# MCU.net
KiCad netlist of a schematic drawn in Altium Designer
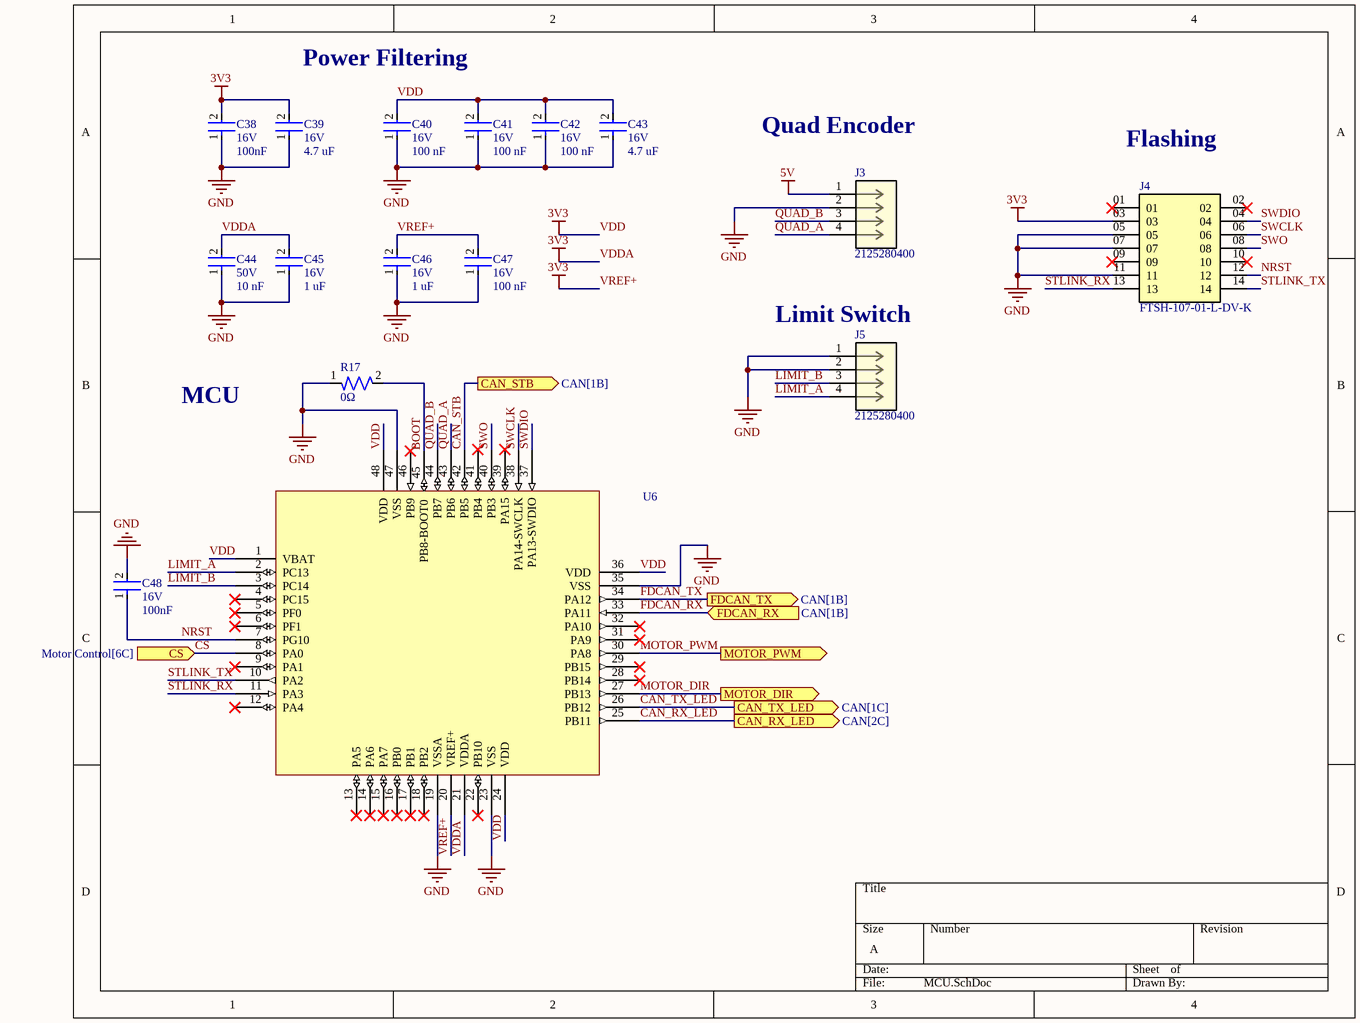
[diagram p0: MCU.SchDoc]

(export (version "E")
  (design (tool "Eeschema 10.0.6"))
  (components
    (comp (ref "C38")
      (value "CAP 0805")
      (footprint "CAP-0805")
      (fields (field (name "VOLTAGE RATING") "16V") (field (name "CAPACITANCE") "100nF"))
      (libsource (lib "EHW_27") (part "CAP 0805"))
    )
    (comp (ref "C39")
      (value "CAP 0805")
      (footprint "CAP-0805")
      (fields (field (name "VOLTAGE RATING") "16V") (field (name "CAPACITANCE") "4.7 uF"))
      (libsource (lib "EHW_27") (part "CAP 0805"))
    )
    (comp (ref "C40")
      (value "CAP 0805")
      (footprint "CAP-0805")
      (fields (field (name "VOLTAGE RATING") "16V") (field (name "CAPACITANCE") "100 nF"))
      (libsource (lib "EHW_27") (part "CAP 0805"))
    )
    (comp (ref "C41")
      (value "CAP 0805")
      (footprint "CAP-0805")
      (fields (field (name "VOLTAGE RATING") "16V") (field (name "CAPACITANCE") "100 nF"))
      (libsource (lib "EHW_27") (part "CAP 0805"))
    )
    (comp (ref "C42")
      (value "CAP 0805")
      (footprint "CAP-0805")
      (fields (field (name "VOLTAGE RATING") "16V") (field (name "CAPACITANCE") "100 nF"))
      (libsource (lib "EHW_27") (part "CAP 0805"))
    )
    (comp (ref "C43")
      (value "CAP 0805")
      (footprint "CAP-0805")
      (fields (field (name "VOLTAGE RATING") "16V") (field (name "CAPACITANCE") "4.7 uF"))
      (libsource (lib "EHW_27") (part "CAP 0805"))
    )
    (comp (ref "C44")
      (value "CAP 0805")
      (footprint "CAP-0805")
      (fields (field (name "VOLTAGE RATING") "50V") (field (name "CAPACITANCE") "10 nF"))
      (libsource (lib "EHW_27") (part "CAP 0805"))
    )
    (comp (ref "C45")
      (value "CAP 0805")
      (footprint "CAP-0805")
      (fields (field (name "VOLTAGE RATING") "16V") (field (name "CAPACITANCE") "1 uF"))
      (libsource (lib "EHW_27") (part "CAP 0805"))
    )
    (comp (ref "C46")
      (value "CAP 0805")
      (footprint "CAP-0805")
      (fields (field (name "VOLTAGE RATING") "16V") (field (name "CAPACITANCE") "1 uF"))
      (libsource (lib "EHW_27") (part "CAP 0805"))
    )
    (comp (ref "C47")
      (value "CAP 0805")
      (footprint "CAP-0805")
      (fields (field (name "VOLTAGE RATING") "16V") (field (name "CAPACITANCE") "100 nF"))
      (libsource (lib "EHW_27") (part "CAP 0805"))
    )
    (comp (ref "C48")
      (value "CAP 0805")
      (footprint "CAP-0805")
      (fields (field (name "VOLTAGE RATING") "16V") (field (name "CAPACITANCE") "100nF"))
      (libsource (lib "EHW_27") (part "CAP 0805"))
    )
    (comp (ref "J3")
      (value "2125280400")
      (footprint "CONN_2125280000_04_MOL")
      (fields (field (name "COPYRIGHT") "Copyright (C) 2026 Ultra Librarian. All rights reserved."))
      (libsource (lib "EHW_27") (part "CONN MF+ 4 PIN Right Angle Square"))
    )
    (comp (ref "J4")
      (value "FTSH-107-01-L-DV-K")
      (footprint "SAMTEC_FTSH-107-01-L-DV-K")
      (description "Connector Header Surface Mount 14 position 0.050\" (1.27mm)")
      (fields (field (name "MF") "Samtec"))
      (libsource (lib "EHW_27") (part "CONN_Flashing-0001"))
    )
    (comp (ref "J5")
      (value "2125280400")
      (footprint "CONN_2125280000_04_MOL")
      (fields (field (name "COPYRIGHT") "Copyright (C) 2026 Ultra Librarian. All rights reserved."))
      (libsource (lib "EHW_27") (part "CONN MF+ 4 PIN Right Angle Square"))
    )
    (comp (ref "R17")
      (value "CRF2010-J/-000ELF")
      (footprint "RES-2010")
      (description "0 Ohms Jumper Chip Resistor 2010 (5025 Metric) Automotive AEC-Q200 Metal Element")
      (fields (field (name "TOLERANCE") "1%") (field (name "RESISTANCE") "0Ω"))
      (libsource (lib "EHW_27") (part "RES-0-0001"))
    )
    (comp (ref "U6")
      (value "STM32G431CBT6")
      (footprint "IC-LQFP48")
      (description "IC MCU 32BIT 128KB FLASH 48LQFP")
      (libsource (lib "EHW_27") (part "IC-STM32G431CBT6"))
    )
  )
  (nets
    (net (code "1") (name "/BOOT") (class "Default")
      (node (ref "R17") (pin "2") (pinfunction "2_2") (pintype "passive"))
      (node (ref "U6") (pin "45") (pinfunction "PB8-BOOT0_45") (pintype "bidirectional"))
    )
    (net (code "2") (name "/CAN_RX_LED") (class "Default")
      (node (ref "U6") (pin "25") (pinfunction "PB11_25") (pintype "output"))
    )
    (net (code "3") (name "/CAN_STB") (class "Default")
      (node (ref "U6") (pin "42") (pinfunction "PB5_42") (pintype "bidirectional"))
    )
    (net (code "4") (name "/CAN_TX_LED") (class "Default")
      (node (ref "U6") (pin "26") (pinfunction "PB12_26") (pintype "output"))
    )
    (net (code "5") (name "/CS") (class "Default")
      (node (ref "U6") (pin "8") (pinfunction "PA0_8") (pintype "bidirectional"))
    )
    (net (code "6") (name "/FDCAN_RX") (class "Default")
      (node (ref "U6") (pin "33") (pinfunction "PA11_33") (pintype "input"))
    )
    (net (code "7") (name "/FDCAN_TX") (class "Default")
      (node (ref "U6") (pin "34") (pinfunction "PA12_34") (pintype "output"))
    )
    (net (code "8") (name "/LIMIT_A") (class "Default")
      (node (ref "J5") (pin "4") (pinfunction "4_4") (pintype "passive"))
      (node (ref "U6") (pin "2") (pinfunction "PC13_2") (pintype "bidirectional"))
    )
    (net (code "9") (name "/LIMIT_B") (class "Default")
      (node (ref "J5") (pin "3") (pinfunction "3_3") (pintype "passive"))
      (node (ref "U6") (pin "3") (pinfunction "PC14_3") (pintype "bidirectional"))
    )
    (net (code "10") (name "/MOTOR_DIR") (class "Default")
      (node (ref "U6") (pin "27") (pinfunction "PB13_27") (pintype "output"))
    )
    (net (code "11") (name "/MOTOR_PWM") (class "Default")
      (node (ref "U6") (pin "30") (pinfunction "PA8_30") (pintype "output"))
    )
    (net (code "12") (name "/NRST") (class "Default")
      (node (ref "C48") (pin "1") (pinfunction "1_1") (pintype "passive"))
      (node (ref "J4") (pin "12") (pinfunction "12_12") (pintype "passive"))
      (node (ref "U6") (pin "7") (pinfunction "PG10_7") (pintype "bidirectional"))
    )
    (net (code "13") (name "/QUAD_A") (class "Default")
      (node (ref "J3") (pin "4") (pinfunction "4_4") (pintype "passive"))
      (node (ref "U6") (pin "43") (pinfunction "PB6_43") (pintype "bidirectional"))
    )
    (net (code "14") (name "/QUAD_B") (class "Default")
      (node (ref "J3") (pin "3") (pinfunction "3_3") (pintype "passive"))
      (node (ref "U6") (pin "44") (pinfunction "PB7_44") (pintype "bidirectional"))
    )
    (net (code "15") (name "/STLINK_RX") (class "Default")
      (node (ref "J4") (pin "13") (pinfunction "13_13") (pintype "passive"))
      (node (ref "U6") (pin "11") (pinfunction "PA3_11") (pintype "input"))
    )
    (net (code "16") (name "/STLINK_TX") (class "Default")
      (node (ref "J4") (pin "14") (pinfunction "14_14") (pintype "passive"))
      (node (ref "U6") (pin "10") (pinfunction "PA2_10") (pintype "output"))
    )
    (net (code "17") (name "/SWCLK") (class "Default")
      (node (ref "J4") (pin "06") (pinfunction "06_06") (pintype "passive"))
      (node (ref "U6") (pin "38") (pinfunction "PA14-SWCLK_38") (pintype "input"))
    )
    (net (code "18") (name "/SWDIO") (class "Default")
      (node (ref "J4") (pin "04") (pinfunction "04_04") (pintype "passive"))
      (node (ref "U6") (pin "37") (pinfunction "PA13-SWDIO_37") (pintype "input"))
    )
    (net (code "19") (name "/SWO") (class "Default")
      (node (ref "J4") (pin "08") (pinfunction "08_08") (pintype "passive"))
      (node (ref "U6") (pin "40") (pinfunction "PB3_40") (pintype "bidirectional"))
    )
    (net (code "20") (name "3V3") (class "Default")
      (node (ref "C38") (pin "2") (pinfunction "2_2") (pintype "passive"))
      (node (ref "C39") (pin "2") (pinfunction "2_2") (pintype "passive"))
      (node (ref "C40") (pin "2") (pinfunction "2_2") (pintype "passive"))
      (node (ref "C41") (pin "2") (pinfunction "2_2") (pintype "passive"))
      (node (ref "C42") (pin "2") (pinfunction "2_2") (pintype "passive"))
      (node (ref "C43") (pin "2") (pinfunction "2_2") (pintype "passive"))
      (node (ref "C44") (pin "2") (pinfunction "2_2") (pintype "passive"))
      (node (ref "C45") (pin "2") (pinfunction "2_2") (pintype "passive"))
      (node (ref "C46") (pin "2") (pinfunction "2_2") (pintype "passive"))
      (node (ref "C47") (pin "2") (pinfunction "2_2") (pintype "passive"))
      (node (ref "J4") (pin "03") (pinfunction "03_03") (pintype "passive"))
      (node (ref "U6") (pin "1") (pinfunction "VBAT_1") (pintype "power_in"))
      (node (ref "U6") (pin "20") (pinfunction "VREF+_20") (pintype "power_in"))
      (node (ref "U6") (pin "21") (pinfunction "VDDA_21") (pintype "power_in"))
      (node (ref "U6") (pin "24") (pinfunction "VDD_24") (pintype "power_in"))
      (node (ref "U6") (pin "36") (pinfunction "VDD_36") (pintype "power_in"))
      (node (ref "U6") (pin "48") (pinfunction "VDD_48") (pintype "power_in"))
    )
    (net (code "21") (name "5V") (class "Default")
      (node (ref "J3") (pin "1") (pinfunction "1_1") (pintype "passive"))
    )
    (net (code "22") (name "GND") (class "Default")
      (node (ref "C38") (pin "1") (pinfunction "1_1") (pintype "passive"))
      (node (ref "C39") (pin "1") (pinfunction "1_1") (pintype "passive"))
      (node (ref "C40") (pin "1") (pinfunction "1_1") (pintype "passive"))
      (node (ref "C41") (pin "1") (pinfunction "1_1") (pintype "passive"))
      (node (ref "C42") (pin "1") (pinfunction "1_1") (pintype "passive"))
      (node (ref "C43") (pin "1") (pinfunction "1_1") (pintype "passive"))
      (node (ref "C44") (pin "1") (pinfunction "1_1") (pintype "passive"))
      (node (ref "C45") (pin "1") (pinfunction "1_1") (pintype "passive"))
      (node (ref "C46") (pin "1") (pinfunction "1_1") (pintype "passive"))
      (node (ref "C47") (pin "1") (pinfunction "1_1") (pintype "passive"))
      (node (ref "C48") (pin "2") (pinfunction "2_2") (pintype "passive"))
      (node (ref "J3") (pin "2") (pinfunction "2_2") (pintype "passive"))
      (node (ref "J4") (pin "05") (pinfunction "05_05") (pintype "passive"))
      (node (ref "J4") (pin "07") (pinfunction "07_07") (pintype "passive"))
      (node (ref "J4") (pin "11") (pinfunction "11_11") (pintype "passive"))
      (node (ref "J5") (pin "1") (pinfunction "1_1") (pintype "passive"))
      (node (ref "J5") (pin "2") (pinfunction "2_2") (pintype "passive"))
      (node (ref "R17") (pin "1") (pinfunction "1_1") (pintype "passive"))
      (node (ref "U6") (pin "19") (pinfunction "VSSA_19") (pintype "power_in"))
      (node (ref "U6") (pin "23") (pinfunction "VSS_23") (pintype "power_in"))
      (node (ref "U6") (pin "35") (pinfunction "VSS_35") (pintype "power_in"))
      (node (ref "U6") (pin "47") (pinfunction "VSS_47") (pintype "power_in"))
    )
    (net (code "23") (name "unconnected-(J4-Pad01)") (class "Default")
      (node (ref "J4") (pin "01") (pinfunction "01_01") (pintype "passive+no_connect"))
    )
    (net (code "24") (name "unconnected-(J4-Pad02)") (class "Default")
      (node (ref "J4") (pin "02") (pinfunction "02_02") (pintype "passive+no_connect"))
    )
    (net (code "25") (name "unconnected-(J4-Pad09)") (class "Default")
      (node (ref "J4") (pin "09") (pinfunction "09_09") (pintype "passive+no_connect"))
    )
    (net (code "26") (name "unconnected-(J4-Pad10)") (class "Default")
      (node (ref "J4") (pin "10") (pinfunction "10_10") (pintype "passive+no_connect"))
    )
    (net (code "27") (name "unconnected-(U6-PA1-Pad9)") (class "Default")
      (node (ref "U6") (pin "9") (pinfunction "PA1_9") (pintype "bidirectional+no_connect"))
    )
    (net (code "28") (name "unconnected-(U6-PA4-Pad12)") (class "Default")
      (node (ref "U6") (pin "12") (pinfunction "PA4_12") (pintype "bidirectional+no_connect"))
    )
    (net (code "29") (name "unconnected-(U6-PA5-Pad13)") (class "Default")
      (node (ref "U6") (pin "13") (pinfunction "PA5_13") (pintype "bidirectional+no_connect"))
    )
    (net (code "30") (name "unconnected-(U6-PA6-Pad14)") (class "Default")
      (node (ref "U6") (pin "14") (pinfunction "PA6_14") (pintype "bidirectional+no_connect"))
    )
    (net (code "31") (name "unconnected-(U6-PA7-Pad15)") (class "Default")
      (node (ref "U6") (pin "15") (pinfunction "PA7_15") (pintype "bidirectional+no_connect"))
    )
    (net (code "32") (name "unconnected-(U6-PA9-Pad31)") (class "Default")
      (node (ref "U6") (pin "31") (pinfunction "PA9_31") (pintype "output+no_connect"))
    )
    (net (code "33") (name "unconnected-(U6-PA10-Pad32)") (class "Default")
      (node (ref "U6") (pin "32") (pinfunction "PA10_32") (pintype "output+no_connect"))
    )
    (net (code "34") (name "unconnected-(U6-PA15-Pad39)") (class "Default")
      (node (ref "U6") (pin "39") (pinfunction "PA15_39") (pintype "bidirectional+no_connect"))
    )
    (net (code "35") (name "unconnected-(U6-PB0-Pad16)") (class "Default")
      (node (ref "U6") (pin "16") (pinfunction "PB0_16") (pintype "bidirectional+no_connect"))
    )
    (net (code "36") (name "unconnected-(U6-PB1-Pad17)") (class "Default")
      (node (ref "U6") (pin "17") (pinfunction "PB1_17") (pintype "bidirectional+no_connect"))
    )
    (net (code "37") (name "unconnected-(U6-PB2-Pad18)") (class "Default")
      (node (ref "U6") (pin "18") (pinfunction "PB2_18") (pintype "bidirectional+no_connect"))
    )
    (net (code "38") (name "unconnected-(U6-PB4-Pad41)") (class "Default")
      (node (ref "U6") (pin "41") (pinfunction "PB4_41") (pintype "bidirectional+no_connect"))
    )
    (net (code "39") (name "unconnected-(U6-PB9-Pad46)") (class "Default")
      (node (ref "U6") (pin "46") (pinfunction "PB9_46") (pintype "input"))
    )
    (net (code "40") (name "unconnected-(U6-PB10-Pad22)") (class "Default")
      (node (ref "U6") (pin "22") (pinfunction "PB10_22") (pintype "bidirectional+no_connect"))
    )
    (net (code "41") (name "unconnected-(U6-PB14-Pad28)") (class "Default")
      (node (ref "U6") (pin "28") (pinfunction "PB14_28") (pintype "output+no_connect"))
    )
    (net (code "42") (name "unconnected-(U6-PB15-Pad29)") (class "Default")
      (node (ref "U6") (pin "29") (pinfunction "PB15_29") (pintype "output+no_connect"))
    )
    (net (code "43") (name "unconnected-(U6-PC15-Pad4)") (class "Default")
      (node (ref "U6") (pin "4") (pinfunction "PC15_4") (pintype "bidirectional+no_connect"))
    )
    (net (code "44") (name "unconnected-(U6-PF0-Pad5)") (class "Default")
      (node (ref "U6") (pin "5") (pinfunction "PF0_5") (pintype "bidirectional+no_connect"))
    )
    (net (code "45") (name "unconnected-(U6-PF1-Pad6)") (class "Default")
      (node (ref "U6") (pin "6") (pinfunction "PF1_6") (pintype "bidirectional+no_connect"))
    )
  )
)
